# 3_InfoPerif.net
KiCad netlist of a schematic drawn in Altium Designer
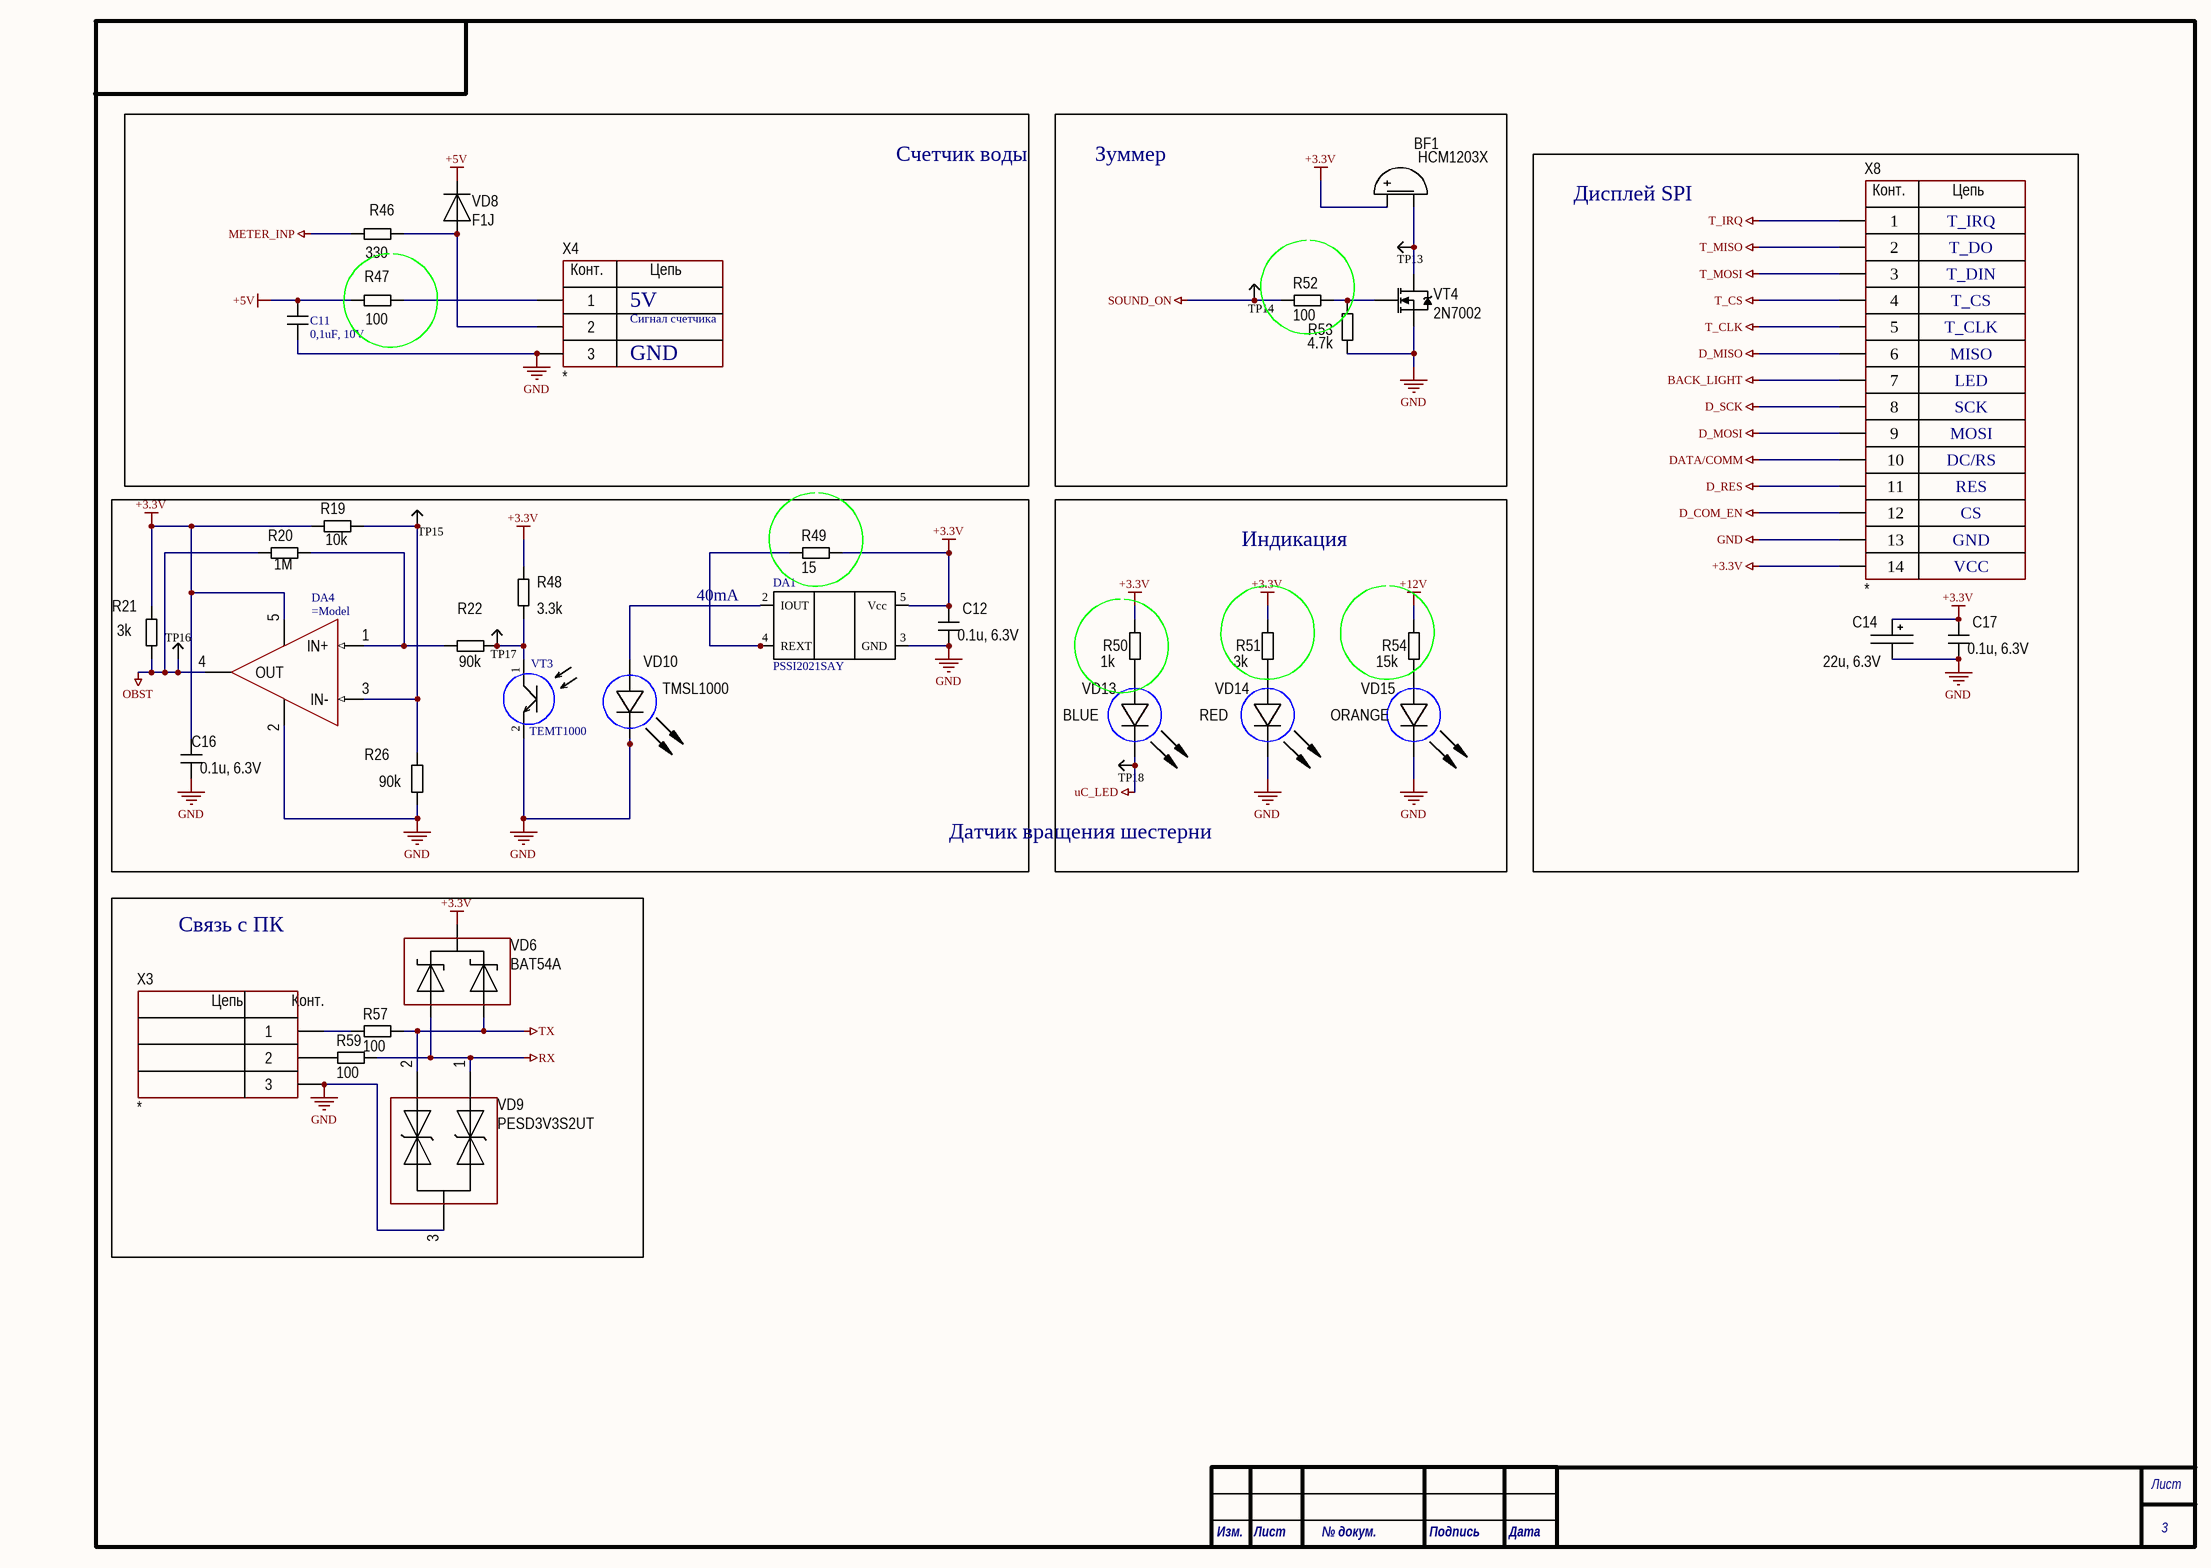
[diagram p0: 3_InfoPerif.SchDoc]

(export (version "E")
  (design (tool "Eeschema 10.0.6"))
  (components
    (comp (ref "BF1")
      (value "HCM1203X")
      (footprint "BUZ: AI-1223-TWT-3V-2-R")
      (fields (field (name "MANUFACTURER") "PUI Audio, Inc."))
      (libsource (lib "Melochi") (part "Buzzer"))
    )
    (comp (ref "C11")
      (value "0,1uF, 10V")
      (footprint "C_0603")
      (libsource (lib "Condensators") (part "C_SMD"))
    )
    (comp (ref "C12")
      (value "0.1u, 6.3V")
      (footprint "CH0805C")
      (description "0805")
      (libsource (lib "Condensators") (part "Capacitor"))
    )
    (comp (ref "C14")
      (value "22u, 6.3V")
      (footprint "TANTAL_B")
      (libsource (lib "Condensators") (part "TantalCap"))
    )
    (comp (ref "C16")
      (value "0.1u, 6.3V")
      (footprint "CH0805C")
      (description "0805")
      (libsource (lib "Condensators") (part "Capacitor"))
    )
    (comp (ref "C17")
      (value "0.1u, 6.3V")
      (footprint "CH0805C")
      (libsource (lib "Condensators") (part "Capacitor"))
    )
    (comp (ref "DA1")
      (value "PSSI2021SAY")
      (footprint "SOT353")
      (description "Iout = 0.617/Rext + 15 µA")
      (libsource (lib "MicroIC") (part "PSSI2021SAY"))
    )
    (comp (ref "DA4")
      (value "~")
      (footprint "SOT23-5")
      (description "SOT23-5")
      (libsource (lib "MicroIC") (part "LMV331M5"))
    )
    (comp (ref "R19") (value "10k") (footprint "CH0603R") (libsource (lib "Resistors") (part "Resistor")))
    (comp (ref "R20") (value "1M") (footprint "CH0603R") (libsource (lib "Resistors") (part "Resistor")))
    (comp (ref "R21") (value "3k") (footprint "CH0603R") (libsource (lib "Resistors") (part "Resistor")))
    (comp (ref "R22") (value "90k") (footprint "CH0805R") (libsource (lib "Resistors") (part "Resistor")))
    (comp (ref "R26") (value "90k") (footprint "CH0603R") (libsource (lib "Resistors") (part "Resistor")))
    (comp (ref "R46") (value "330") (footprint "CH0603R") (libsource (lib "Resistors") (part "Resistor")))
    (comp (ref "R47") (value "100") (footprint "CH2512R") (libsource (lib "Resistors") (part "Resistor")))
    (comp (ref "R48")
      (value "3.3k")
      (footprint "CH0603R")
      (description "0805")
      (libsource (lib "Resistors") (part "Resistor"))
    )
    (comp (ref "R49")
      (value "15")
      (footprint "CH0805R")
      (description "0805")
      (libsource (lib "Resistors") (part "Resistor"))
    )
    (comp (ref "R50") (value "1k") (footprint "CH0805R") (libsource (lib "Resistors") (part "Resistor")))
    (comp (ref "R51") (value "3k") (footprint "CH0805R") (libsource (lib "Resistors") (part "Resistor")))
    (comp (ref "R52") (value "100") (footprint "CH0805R") (libsource (lib "Resistors") (part "Resistor")))
    (comp (ref "R53") (value "4.7k") (footprint "CH0603R") (libsource (lib "Resistors") (part "Resistor")))
    (comp (ref "R54") (value "15k") (footprint "CH0805R") (libsource (lib "Resistors") (part "Resistor")))
    (comp (ref "R57") (value "100") (footprint "CH0603R") (libsource (lib "Resistors") (part "Resistor")))
    (comp (ref "R59") (value "100") (footprint "CH0603R") (libsource (lib "Resistors") (part "Resistor")))
    (comp (ref "TP13") (value "~") (footprint "TestPoint") (libsource (lib "Melochi") (part "TestPoint")))
    (comp (ref "TP14") (value "~") (footprint "TestPoint") (libsource (lib "Melochi") (part "TestPoint")))
    (comp (ref "TP15") (value "~") (footprint "TestPoint") (libsource (lib "Melochi") (part "TestPoint")))
    (comp (ref "TP16") (value "~") (footprint "TestPoint") (libsource (lib "Melochi") (part "TestPoint")))
    (comp (ref "TP17") (value "~") (footprint "TestPoint") (libsource (lib "Melochi") (part "TestPoint")))
    (comp (ref "TP18") (value "~") (footprint "TestPoint") (libsource (lib "Melochi") (part "TestPoint")))
    (comp (ref "VD6")
      (value "BAT54A")
      (footprint "SOT23_123")
      (libsource (lib "Diods") (part "Diod Schottky Array v.1"))
    )
    (comp (ref "VD8") (value "F1J") (footprint "SOD123F") (libsource (lib "Diods") (part "Diod")))
    (comp (ref "VD9")
      (value "PESD3V3S2UT")
      (footprint "SOT23_132")
      (libsource (lib "Diods") (part "TVS Array"))
    )
    (comp (ref "VD10") (value "TMSL1000") (footprint "TSML1000") (libsource (lib "Diods") (part "LED_1")))
    (comp (ref "VD13") (value "BLUE") (footprint "CH0603LB") (libsource (lib "Diods") (part "LED_1")))
    (comp (ref "VD14") (value "RED") (footprint "CH0603LB") (libsource (lib "Diods") (part "LED_1")))
    (comp (ref "VD15") (value "ORANGE") (footprint "CH0603LB") (libsource (lib "Diods") (part "LED_1")))
    (comp (ref "VT3")
      (value "TEMT1000")
      (footprint "TEMT1000")
      (libsource (lib "Tranzistor") (part "TEMT1000"))
    )
    (comp (ref "VT4")
      (value "2N7002")
      (footprint "SOT23_123")
      (description "Mosfet")
      (libsource (lib "Tranzistor") (part "N-chanel"))
    )
    (comp (ref "X3") (value "*") (footprint "CON: CWF-3") (libsource (lib "") (part "3-Connector_1")))
    (comp (ref "X4") (value "*") (footprint "CON: CWF-3") (libsource (lib "Connectors") (part "3-Connector")))
    (comp (ref "X8") (value "*") (footprint "DS1024-14") (libsource (lib "Connectors") (part "14-Connector")))
  )
  (nets
    (net (code "1") (name "+3.3V") (class "Default")
      (node (ref "BF1") (pin "1") (pinfunction "+_1") (pintype "passive"))
      (node (ref "C12") (pin "2") (pinfunction "2_2") (pintype "passive"))
      (node (ref "C14") (pin "1") (pinfunction "1_1") (pintype "power_in"))
      (node (ref "C16") (pin "2") (pinfunction "2_2") (pintype "passive"))
      (node (ref "C17") (pin "2") (pinfunction "2_2") (pintype "passive"))
      (node (ref "DA4") (pin "5") (pinfunction "V+_5") (pintype "power_in"))
      (node (ref "R19") (pin "2") (pinfunction "2_2") (pintype "passive"))
      (node (ref "R21") (pin "2") (pinfunction "2_2") (pintype "passive"))
      (node (ref "R48") (pin "2") (pinfunction "2_2") (pintype "passive"))
      (node (ref "R49") (pin "2") (pinfunction "2_2") (pintype "passive"))
      (node (ref "R50") (pin "2") (pinfunction "2_2") (pintype "passive"))
      (node (ref "R51") (pin "2") (pinfunction "2_2") (pintype "passive"))
      (node (ref "VD6") (pin "2") (pinfunction "2_2") (pintype "passive"))
      (node (ref "X8") (pin "14") (pinfunction "14_14") (pintype "power_in"))
    )
    (net (code "2") (name "+5V") (class "Default")
      (node (ref "C11") (pin "2") (pinfunction "2_2") (pintype "passive"))
      (node (ref "R47") (pin "1") (pinfunction "1_1") (pintype "passive"))
      (node (ref "VD8") (pin "2") (pinfunction "2_2") (pintype "passive"))
    )
    (net (code "3") (name "+12V") (class "Default")
      (node (ref "R54") (pin "2") (pinfunction "2_2") (pintype "passive"))
    )
    (net (code "4") (name "BACK_LIGHT") (class "Default")
      (node (ref "X8") (pin "7") (pinfunction "7_7") (pintype "power_in"))
    )
    (net (code "5") (name "DATA{slash}COMM") (class "Default")
      (node (ref "X8") (pin "10") (pinfunction "10_10") (pintype "power_in"))
    )
    (net (code "6") (name "D_COM_EN") (class "Default")
      (node (ref "X8") (pin "12") (pinfunction "12_12") (pintype "power_in"))
    )
    (net (code "7") (name "D_MISO") (class "Default")
      (node (ref "X8") (pin "6") (pinfunction "6_6") (pintype "power_in"))
    )
    (net (code "8") (name "D_MOSI") (class "Default")
      (node (ref "X8") (pin "9") (pinfunction "9_9") (pintype "power_in"))
    )
    (net (code "9") (name "D_RES") (class "Default")
      (node (ref "X8") (pin "11") (pinfunction "11_11") (pintype "power_in"))
    )
    (net (code "10") (name "D_SCK") (class "Default")
      (node (ref "X8") (pin "8") (pinfunction "8_8") (pintype "power_in"))
    )
    (net (code "11") (name "GND") (class "Default")
      (node (ref "C11") (pin "1") (pinfunction "1_1") (pintype "passive"))
      (node (ref "C12") (pin "1") (pinfunction "1_1") (pintype "passive"))
      (node (ref "C14") (pin "2") (pinfunction "2_2") (pintype "power_in"))
      (node (ref "C16") (pin "1") (pinfunction "1_1") (pintype "passive"))
      (node (ref "C17") (pin "1") (pinfunction "1_1") (pintype "passive"))
      (node (ref "DA1") (pin "3") (pinfunction "GND_3") (pintype "passive"))
      (node (ref "DA4") (pin "2") (pinfunction "V-_2") (pintype "power_in"))
      (node (ref "R26") (pin "1") (pinfunction "1_1") (pintype "passive"))
      (node (ref "R53") (pin "1") (pinfunction "1_1") (pintype "passive"))
      (node (ref "VD10") (pin "2") (pinfunction "C_2") (pintype "passive"))
      (node (ref "VD14") (pin "2") (pinfunction "C_2") (pintype "passive"))
      (node (ref "VD15") (pin "2") (pinfunction "C_2") (pintype "passive"))
      (node (ref "VD9") (pin "3") (pintype "passive"))
      (node (ref "VT3") (pin "2") (pinfunction "2_2") (pintype "passive"))
      (node (ref "VT4") (pin "3") (pinfunction "S_3") (pintype "passive"))
      (node (ref "X3") (pin "3") (pinfunction "3_3") (pintype "passive"))
      (node (ref "X4") (pin "3") (pinfunction "3_3") (pintype "passive"))
      (node (ref "X8") (pin "13") (pinfunction "13_13") (pintype "power_in"))
    )
    (net (code "12") (name "METER_INP") (class "Default")
      (node (ref "R46") (pin "1") (pinfunction "1_1") (pintype "passive"))
    )
    (net (code "13") (name "Net-(BF1--)") (class "Default")
      (node (ref "BF1") (pin "2") (pinfunction "-_2") (pintype "passive"))
      (node (ref "TP13") (pin "0") (pinfunction "0_0") (pintype "passive"))
      (node (ref "VT4") (pin "2") (pinfunction "D_2") (pintype "passive"))
    )
    (net (code "14") (name "Net-(DA1-IOUT)") (class "Default")
      (node (ref "DA1") (pin "2") (pinfunction "IOUT_2") (pintype "passive"))
      (node (ref "VD10") (pin "1") (pinfunction "A_1") (pintype "passive"))
    )
    (net (code "15") (name "Net-(DA1-REXT)") (class "Default")
      (node (ref "DA1") (pin "4") (pinfunction "REXT_4") (pintype "passive"))
      (node (ref "R49") (pin "1") (pinfunction "1_1") (pintype "passive"))
    )
    (net (code "16") (name "Net-(DA4-IN+)") (class "Default")
      (node (ref "DA4") (pin "1") (pinfunction "IN+_1") (pintype "input"))
      (node (ref "R20") (pin "1") (pinfunction "1_1") (pintype "passive"))
      (node (ref "R22") (pin "2") (pinfunction "2_2") (pintype "passive"))
    )
    (net (code "17") (name "Net-(DA4-IN-)") (class "Default")
      (node (ref "DA4") (pin "3") (pinfunction "IN-_3") (pintype "input"))
      (node (ref "R19") (pin "1") (pinfunction "1_1") (pintype "passive"))
      (node (ref "R26") (pin "2") (pinfunction "2_2") (pintype "passive"))
      (node (ref "TP15") (pin "0") (pinfunction "0_0") (pintype "passive"))
    )
    (net (code "18") (name "Net-(R22-Pad1)") (class "Default")
      (node (ref "R22") (pin "1") (pinfunction "1_1") (pintype "passive"))
      (node (ref "R48") (pin "1") (pinfunction "1_1") (pintype "passive"))
      (node (ref "TP17") (pin "0") (pinfunction "0_0") (pintype "passive"))
      (node (ref "VT3") (pin "1") (pinfunction "1_1") (pintype "passive"))
    )
    (net (code "19") (name "Net-(R46-Pad2)") (class "Default")
      (node (ref "R46") (pin "2") (pinfunction "2_2") (pintype "passive"))
      (node (ref "VD8") (pin "1") (pinfunction "1_1") (pintype "passive"))
      (node (ref "X4") (pin "2") (pinfunction "2_2") (pintype "passive"))
    )
    (net (code "20") (name "Net-(R47-Pad2)") (class "Default")
      (node (ref "R47") (pin "2") (pinfunction "2_2") (pintype "passive"))
      (node (ref "X4") (pin "1") (pinfunction "1_1") (pintype "passive"))
    )
    (net (code "21") (name "Net-(R57-Pad1)") (class "Default")
      (node (ref "R57") (pin "1") (pinfunction "1_1") (pintype "passive"))
      (node (ref "X3") (pin "1") (pinfunction "1_1") (pintype "passive"))
    )
    (net (code "22") (name "Net-(R59-Pad1)") (class "Default")
      (node (ref "R59") (pin "1") (pinfunction "1_1") (pintype "passive"))
      (node (ref "X3") (pin "2") (pinfunction "2_2") (pintype "passive"))
    )
    (net (code "23") (name "Net-(VD13-A)") (class "Default")
      (node (ref "R50") (pin "1") (pinfunction "1_1") (pintype "passive"))
      (node (ref "VD13") (pin "1") (pinfunction "A_1") (pintype "passive"))
    )
    (net (code "24") (name "Net-(VD14-A)") (class "Default")
      (node (ref "R51") (pin "1") (pinfunction "1_1") (pintype "passive"))
      (node (ref "VD14") (pin "1") (pinfunction "A_1") (pintype "passive"))
    )
    (net (code "25") (name "Net-(VD15-A)") (class "Default")
      (node (ref "R54") (pin "1") (pinfunction "1_1") (pintype "passive"))
      (node (ref "VD15") (pin "1") (pinfunction "A_1") (pintype "passive"))
    )
    (net (code "26") (name "Net-(VT4-G)") (class "Default")
      (node (ref "R52") (pin "1") (pinfunction "1_1") (pintype "passive"))
      (node (ref "R53") (pin "2") (pinfunction "2_2") (pintype "passive"))
      (node (ref "VT4") (pin "1") (pinfunction "G_1") (pintype "passive"))
    )
    (net (code "27") (name "OBST") (class "Default")
      (node (ref "DA4") (pin "4") (pinfunction "OUT_4") (pintype "power_in"))
      (node (ref "R20") (pin "2") (pinfunction "2_2") (pintype "passive"))
      (node (ref "R21") (pin "1") (pinfunction "1_1") (pintype "passive"))
      (node (ref "TP16") (pin "0") (pinfunction "0_0") (pintype "passive"))
    )
    (net (code "28") (name "RX") (class "Default")
      (node (ref "R59") (pin "2") (pinfunction "2_2") (pintype "passive"))
      (node (ref "VD6") (pin "3") (pinfunction "3_3") (pintype "passive"))
      (node (ref "VD9") (pin "1") (pintype "passive"))
    )
    (net (code "29") (name "SOUND_ON") (class "Default")
      (node (ref "R52") (pin "2") (pinfunction "2_2") (pintype "passive"))
      (node (ref "TP14") (pin "0") (pinfunction "0_0") (pintype "passive"))
    )
    (net (code "30") (name "TX") (class "Default")
      (node (ref "R57") (pin "2") (pinfunction "2_2") (pintype "passive"))
      (node (ref "VD6") (pin "1") (pinfunction "1_1") (pintype "passive"))
      (node (ref "VD9") (pin "2") (pintype "passive"))
    )
    (net (code "31") (name "T_CLK") (class "Default")
      (node (ref "X8") (pin "5") (pinfunction "5_5") (pintype "power_in"))
    )
    (net (code "32") (name "T_CS") (class "Default")
      (node (ref "X8") (pin "4") (pinfunction "4_4") (pintype "power_in"))
    )
    (net (code "33") (name "T_IRQ") (class "Default")
      (node (ref "X8") (pin "1") (pinfunction "1_1") (pintype "passive"))
    )
    (net (code "34") (name "T_MISO") (class "Default")
      (node (ref "X8") (pin "2") (pinfunction "2_2") (pintype "passive"))
    )
    (net (code "35") (name "T_MOSI") (class "Default")
      (node (ref "X8") (pin "3") (pinfunction "3_3") (pintype "power_in"))
    )
    (net (code "36") (name "uC_LED") (class "Default")
      (node (ref "TP18") (pin "0") (pinfunction "0_0") (pintype "passive"))
      (node (ref "VD13") (pin "2") (pinfunction "C_2") (pintype "passive"))
    )
    (net (code "37") (name "unconnected-(DA1-Vcc-Pad5)") (class "Default")
      (node (ref "DA1") (pin "5") (pinfunction "Vcc_5") (pintype "passive"))
    )
  )
)
